# casio.net
KiCad netlist of a schematic drawn in Altium Designer
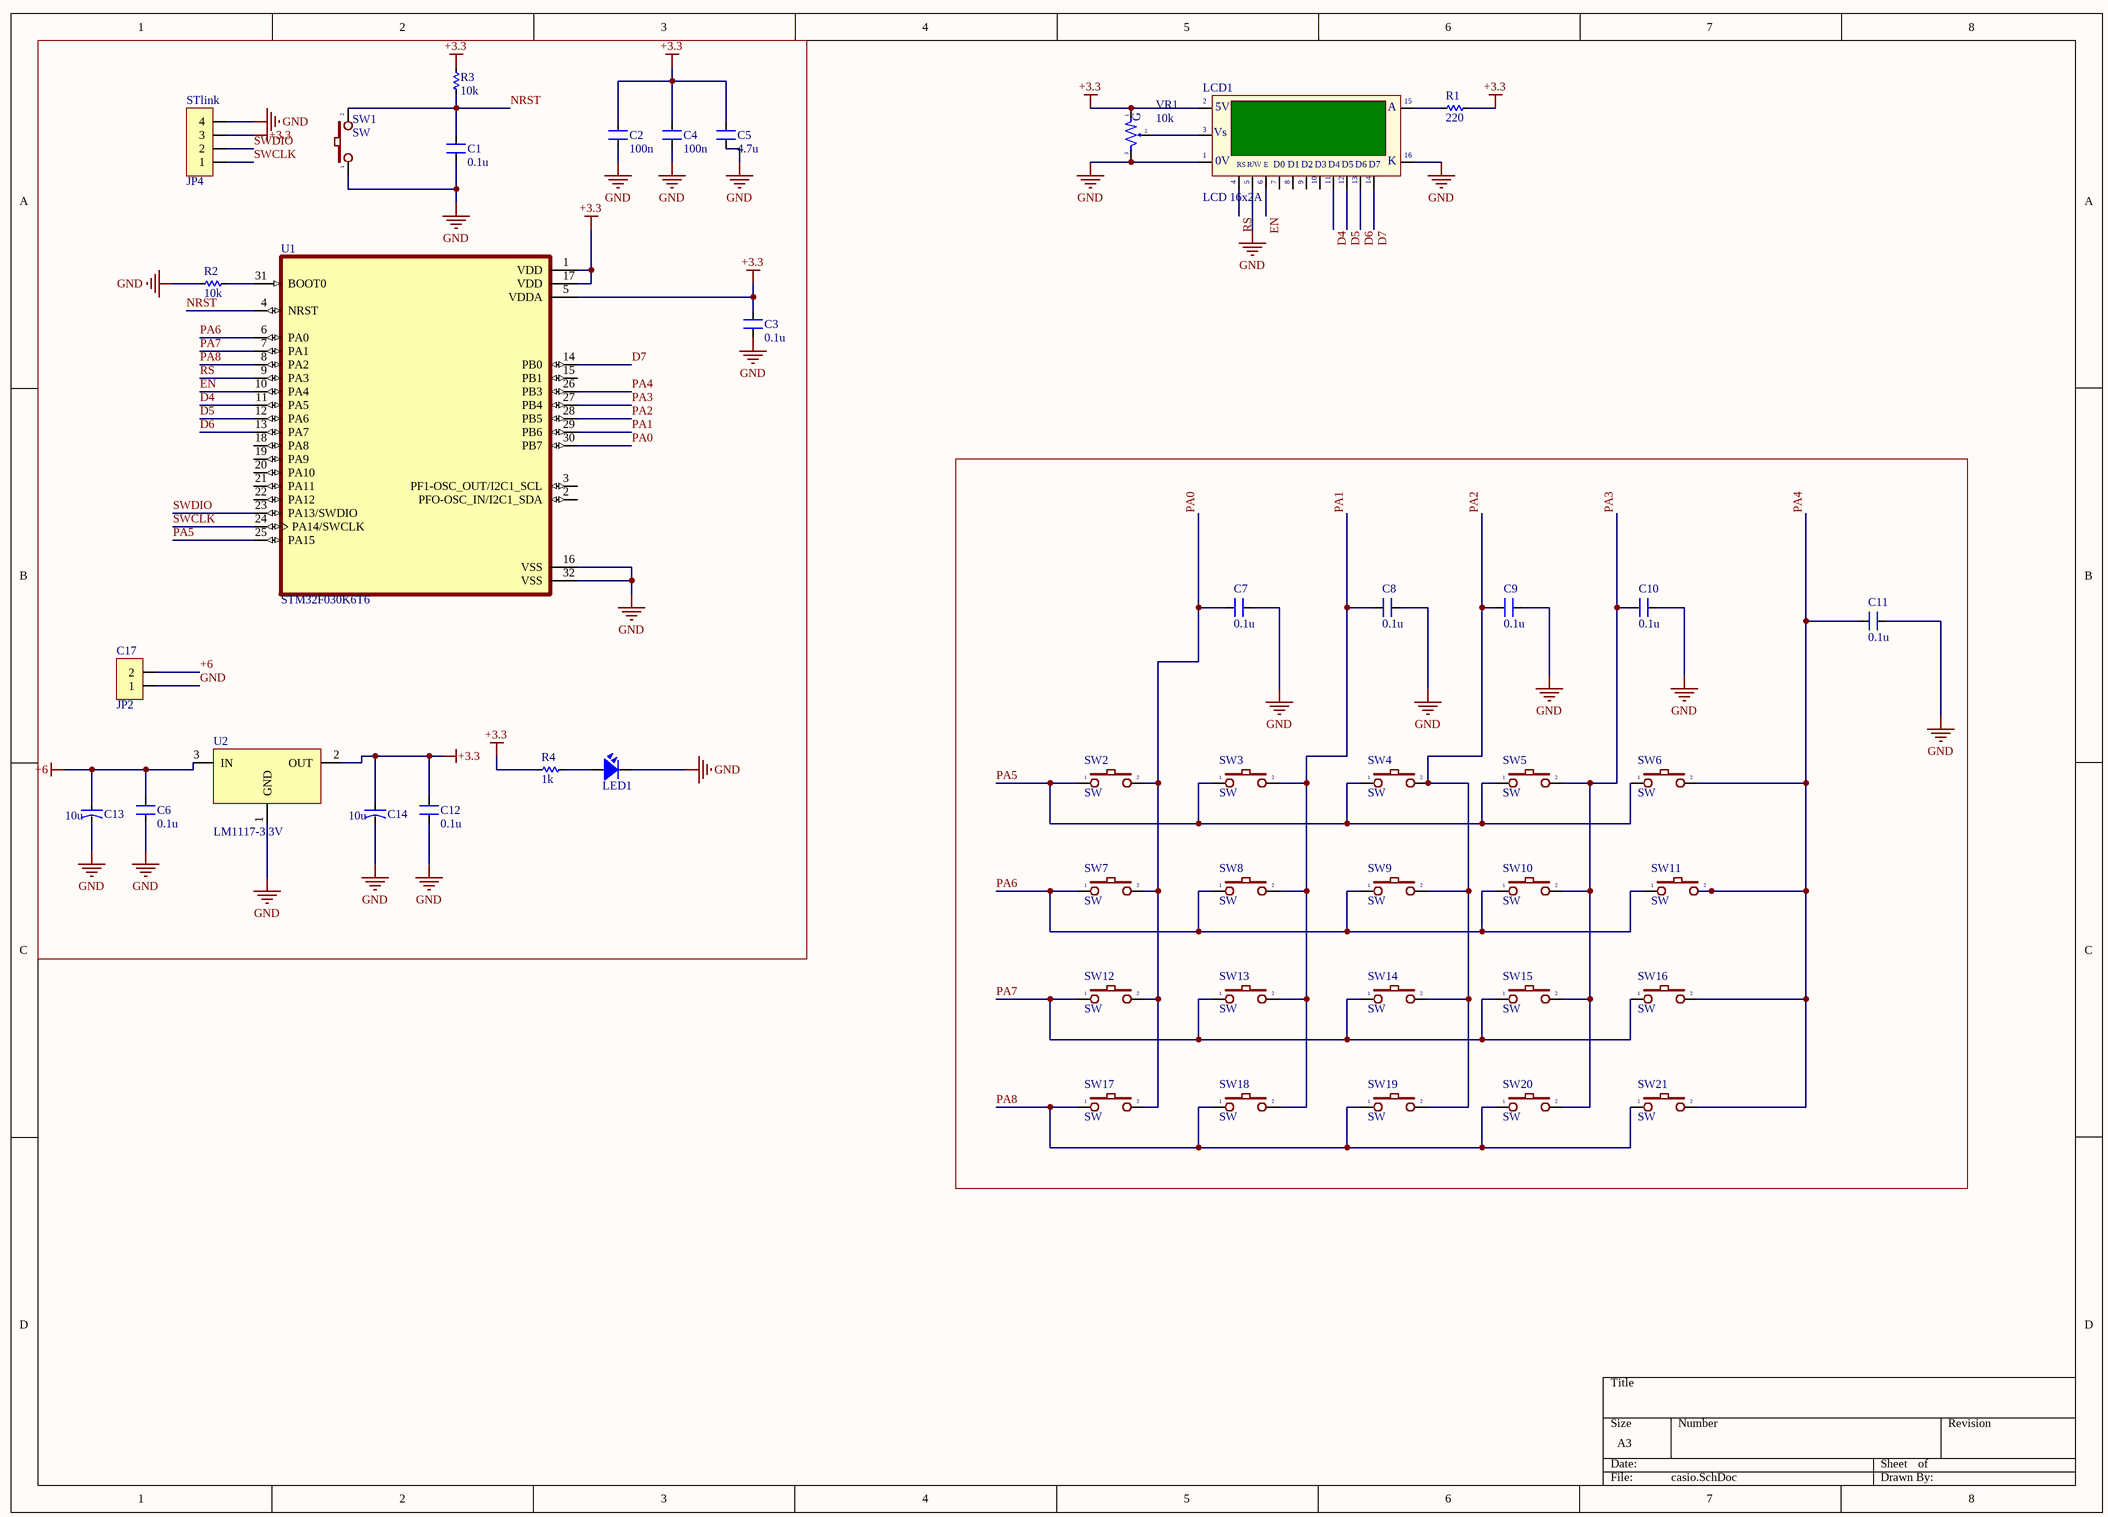
[diagram p0: casio.SchDoc]

(export (version "E")
  (design (tool "Eeschema 10.0.6"))
  (components
    (comp (ref "C1") (value "0.1u") (footprint "CN-SMD-0805") (libsource (lib "Library") (part "CN")))
    (comp (ref "C2") (value "100n") (footprint "CN-SMD-0805") (libsource (lib "Library") (part "CN")))
    (comp (ref "C3") (value "0.1u") (footprint "CN-SMD-0805") (libsource (lib "Library") (part "CN")))
    (comp (ref "C4") (value "100n") (footprint "CN-SMD-0805") (libsource (lib "Library") (part "CN")))
    (comp (ref "C5") (value "4.7u") (footprint "CN-SMD-0805") (libsource (lib "Library") (part "CN")))
    (comp (ref "C6") (value "0.1u") (footprint "CN-SMD-0805") (libsource (lib "Library") (part "CN")))
    (comp (ref "C7") (value "0.1u") (footprint "CN-SMD-0805") (libsource (lib "Library") (part "CN")))
    (comp (ref "C8") (value "0.1u") (footprint "CN-SMD-0805") (libsource (lib "Library") (part "CN")))
    (comp (ref "C9") (value "0.1u") (footprint "CN-SMD-0805") (libsource (lib "Library") (part "CN")))
    (comp (ref "C10") (value "0.1u") (footprint "CN-SMD-0805") (libsource (lib "Library") (part "CN")))
    (comp (ref "C11") (value "0.1u") (footprint "CN-SMD-0805") (libsource (lib "Library") (part "CN")))
    (comp (ref "C12") (value "0.1u") (footprint "CN-SMD-0805") (libsource (lib "Library") (part "CN")))
    (comp (ref "C13")
      (value "10u")
      (footprint "CAP-ALU-SMD-5.5x5.5")
      (description "Polarized Capacitor (Axial)")
      (fields (field (name "PUBLISHER") "Altium Limited"))
      (libsource (lib "Library") (part "CN-SMD"))
    )
    (comp (ref "C14")
      (value "10u")
      (footprint "CAP-ALU-SMD-5.5x5.5")
      (description "Polarized Capacitor (Axial)")
      (fields (field (name "PUBLISHER") "Altium Limited"))
      (libsource (lib "Library") (part "CN-SMD"))
    )
    (comp (ref "C17")
      (value "JP2")
      (footprint "JP2-D1T")
      (description "WR-PHD 2.54 mm Angled Socket Header")
      (fields
        (field (name "MANUFACTURER") "Würth Elektronik eiSos GmbH")
        (field (name "PARTNO") "613002143121")
        (field (name "CREATED BY") "Karrer Zheng")
      )
      (libsource (lib "Library") (part "JP2"))
    )
    (comp (ref "LCD1")
      (value "LCD 16x2A")
      (footprint "LCD16X2")
      (description "LCD dipslay 16 char, 2 line")
      (libsource (lib "Library") (part "LCD16x2A"))
    )
    (comp (ref "LED1") (value "LED") (footprint "LED-0805-Red") (libsource (lib "Library") (part "LED SMD")))
    (comp (ref "R1")
      (value "220")
      (footprint "RES-SMD-0805")
      (description "Resistor")
      (fields
        (field (name "MANUFACTURER") "Generic Components")
        (field (name "PUBLISHER") "Altium Hobart Technology Centre")
      )
      (libsource (lib "Library") (part "Res-SMD"))
    )
    (comp (ref "R2")
      (value "10k")
      (footprint "RES-SMD-0805")
      (description "Resistor")
      (fields
        (field (name "MANUFACTURER") "Generic Components")
        (field (name "PUBLISHER") "Altium Hobart Technology Centre")
      )
      (libsource (lib "Library") (part "Res-SMD"))
    )
    (comp (ref "R3")
      (value "10k")
      (footprint "RES-SMD-0805")
      (description "Resistor")
      (fields
        (field (name "MANUFACTURER") "Generic Components")
        (field (name "PUBLISHER") "Altium Hobart Technology Centre")
      )
      (libsource (lib "Library") (part "Res-SMD"))
    )
    (comp (ref "R4")
      (value "1k")
      (footprint "RES-SMD-0805")
      (description "Resistor")
      (fields
        (field (name "MANUFACTURER") "Generic Components")
        (field (name "PUBLISHER") "Altium Hobart Technology Centre")
      )
      (libsource (lib "Library") (part "Res-SMD"))
    )
    (comp (ref "STlink")
      (value "JP4")
      (footprint "JP4-C1T")
      (description "WR-PHD 2.54 mm Angled Socket Header")
      (fields
        (field (name "MANUFACTURER") "Würth Elektronik eiSos GmbH")
        (field (name "PARTNO") "613004143121")
        (field (name "CREATED BY") "Karrer Zheng")
      )
      (libsource (lib "Library") (part "JP4"))
    )
    (comp (ref "SW1")
      (value "SW")
      (footprint "SW1-SMD")
      (description "Switch button 2 pin")
      (libsource (lib "Library") (part "SW2"))
    )
    (comp (ref "SW2")
      (value "SW")
      (footprint "SW1-DIP-12x12x8-Black")
      (description "Switch button 2 pin")
      (libsource (lib "Library") (part "SW2"))
    )
    (comp (ref "SW3")
      (value "SW")
      (footprint "SW1-DIP-12x12x8-Black")
      (description "Switch button 2 pin")
      (libsource (lib "Library") (part "SW2"))
    )
    (comp (ref "SW4")
      (value "SW")
      (footprint "SW1-DIP-12x12x8-Black")
      (description "Switch button 2 pin")
      (libsource (lib "Library") (part "SW2"))
    )
    (comp (ref "SW5")
      (value "SW")
      (footprint "SW1-DIP-12x12x8-Black")
      (description "Switch button 2 pin")
      (libsource (lib "Library") (part "SW2"))
    )
    (comp (ref "SW6")
      (value "SW")
      (footprint "SW1-DIP-12x12x8-Black")
      (description "Switch button 2 pin")
      (libsource (lib "Library") (part "SW2"))
    )
    (comp (ref "SW7")
      (value "SW")
      (footprint "SW1-DIP-12x12x8-Black")
      (description "Switch button 2 pin")
      (libsource (lib "Library") (part "SW2"))
    )
    (comp (ref "SW8")
      (value "SW")
      (footprint "SW1-DIP-12x12x8-Black")
      (description "Switch button 2 pin")
      (libsource (lib "Library") (part "SW2"))
    )
    (comp (ref "SW9")
      (value "SW")
      (footprint "SW1-DIP-12x12x8-Black")
      (description "Switch button 2 pin")
      (libsource (lib "Library") (part "SW2"))
    )
    (comp (ref "SW10")
      (value "SW")
      (footprint "SW1-DIP-12x12x8-Black")
      (description "Switch button 2 pin")
      (libsource (lib "Library") (part "SW2"))
    )
    (comp (ref "SW11")
      (value "SW")
      (footprint "SW1-DIP-12x12x8-Black")
      (description "Switch button 2 pin")
      (libsource (lib "Library") (part "SW2"))
    )
    (comp (ref "SW12")
      (value "SW")
      (footprint "SW1-DIP-12x12x8-Black")
      (description "Switch button 2 pin")
      (libsource (lib "Library") (part "SW2"))
    )
    (comp (ref "SW13")
      (value "SW")
      (footprint "SW1-DIP-12x12x8-Black")
      (description "Switch button 2 pin")
      (libsource (lib "Library") (part "SW2"))
    )
    (comp (ref "SW14")
      (value "SW")
      (footprint "SW1-DIP-12x12x8-Black")
      (description "Switch button 2 pin")
      (libsource (lib "Library") (part "SW2"))
    )
    (comp (ref "SW15")
      (value "SW")
      (footprint "SW1-DIP-12x12x8-Black")
      (description "Switch button 2 pin")
      (libsource (lib "Library") (part "SW2"))
    )
    (comp (ref "SW16")
      (value "SW")
      (footprint "SW1-DIP-12x12x8-Black")
      (description "Switch button 2 pin")
      (libsource (lib "Library") (part "SW2"))
    )
    (comp (ref "SW17")
      (value "SW")
      (footprint "SW1-DIP-12x12x8-Black")
      (description "Switch button 2 pin")
      (libsource (lib "Library") (part "SW2"))
    )
    (comp (ref "SW18")
      (value "SW")
      (footprint "SW1-DIP-12x12x8-Black")
      (description "Switch button 2 pin")
      (libsource (lib "Library") (part "SW2"))
    )
    (comp (ref "SW19")
      (value "SW")
      (footprint "SW1-DIP-12x12x8-Black")
      (description "Switch button 2 pin")
      (libsource (lib "Library") (part "SW2"))
    )
    (comp (ref "SW20")
      (value "SW")
      (footprint "SW1-DIP-12x12x8-Black")
      (description "Switch button 2 pin")
      (libsource (lib "Library") (part "SW2"))
    )
    (comp (ref "SW21")
      (value "SW")
      (footprint "SW1-DIP-12x12x8-Black")
      (description "Switch button 2 pin")
      (libsource (lib "Library") (part "SW2"))
    )
    (comp (ref "U1")
      (value "STM32F030K6T6")
      (footprint "QFP80P900X900X160-32N")
      (fields (field (name "DIGI-KEY_PART_NUMBER") "497-14046-ND") (field (name "MF") "STMicroelectronics"))
      (libsource (lib "Library") (part "STM32F030K6T6"))
    )
    (comp (ref "U2")
      (value "LM1117-3.3V")
      (footprint "SOT223")
      (description "800mA Low-Dropout Linear Regulator")
      (fields (field (name "CREATOR") "Nguyen Ba Bien"))
      (libsource (lib "Library") (part "LM1117"))
    )
    (comp (ref "VR1")
      (value "10k")
      (footprint "VR-S2")
      (description "Var Resistor")
      (libsource (lib "Library") (part "VR-S"))
    )
  )
  (nets
    (net (code "1") (name "+3.3") (class "Default")
      (node (ref "C12") (pin "1") (pinfunction "1_1") (pintype "passive"))
      (node (ref "C14") (pin "1") (pinfunction "1_1") (pintype "passive"))
      (node (ref "C2") (pin "1") (pinfunction "1_1") (pintype "passive"))
      (node (ref "C3") (pin "1") (pinfunction "1_1") (pintype "passive"))
      (node (ref "C4") (pin "1") (pinfunction "1_1") (pintype "passive"))
      (node (ref "C5") (pin "1") (pinfunction "1_1") (pintype "passive"))
      (node (ref "LCD1") (pin "2") (pinfunction "VDD_2") (pintype "passive"))
      (node (ref "R1") (pin "1") (pinfunction "1_1") (pintype "passive"))
      (node (ref "R3") (pin "2") (pinfunction "2_2") (pintype "passive"))
      (node (ref "R4") (pin "2") (pinfunction "2_2") (pintype "passive"))
      (node (ref "STlink") (pin "3") (pinfunction "3_3") (pintype "passive"))
      (node (ref "U1") (pin "1") (pinfunction "VDD_1") (pintype "power_in"))
      (node (ref "U1") (pin "17") (pinfunction "VDD_17") (pintype "power_in"))
      (node (ref "U1") (pin "5") (pinfunction "VDDA_5") (pintype "power_in"))
      (node (ref "U2") (pin "2") (pinfunction "OUT_2") (pintype "passive"))
      (node (ref "VR1") (pin "1") (pinfunction "1_1") (pintype "passive"))
    )
    (net (code "2") (name "+6") (class "Default")
      (node (ref "C13") (pin "1") (pinfunction "1_1") (pintype "passive"))
      (node (ref "C17") (pin "2") (pinfunction "2_2") (pintype "passive"))
      (node (ref "C6") (pin "1") (pinfunction "1_1") (pintype "passive"))
      (node (ref "U2") (pin "3") (pinfunction "IN_3") (pintype "passive"))
    )
    (net (code "3") (name "/D4") (class "Default")
      (node (ref "LCD1") (pin "11") (pinfunction "D4_11") (pintype "passive"))
      (node (ref "U1") (pin "11") (pinfunction "PA5_11") (pintype "bidirectional"))
    )
    (net (code "4") (name "/D5") (class "Default")
      (node (ref "LCD1") (pin "12") (pinfunction "D5_12") (pintype "passive"))
      (node (ref "U1") (pin "12") (pinfunction "PA6_12") (pintype "bidirectional"))
    )
    (net (code "5") (name "/D6") (class "Default")
      (node (ref "LCD1") (pin "13") (pinfunction "D6_13") (pintype "passive"))
      (node (ref "U1") (pin "13") (pinfunction "PA7_13") (pintype "bidirectional"))
    )
    (net (code "6") (name "/D7") (class "Default")
      (node (ref "LCD1") (pin "14") (pinfunction "D7_14") (pintype "passive"))
      (node (ref "U1") (pin "14") (pinfunction "PB0_14") (pintype "bidirectional"))
    )
    (net (code "7") (name "/EN") (class "Default")
      (node (ref "LCD1") (pin "6") (pinfunction "~{EN}_6") (pintype "passive"))
      (node (ref "U1") (pin "10") (pinfunction "PA4_10") (pintype "bidirectional"))
    )
    (net (code "8") (name "/NRST") (class "Default")
      (node (ref "C1") (pin "1") (pinfunction "1_1") (pintype "passive"))
      (node (ref "R3") (pin "1") (pinfunction "1_1") (pintype "passive"))
      (node (ref "SW1") (pin "2") (pinfunction "2_2") (pintype "passive"))
      (node (ref "U1") (pin "4") (pinfunction "NRST_4") (pintype "bidirectional"))
    )
    (net (code "9") (name "/PA0") (class "Default")
      (node (ref "C7") (pin "1") (pinfunction "1_1") (pintype "passive"))
      (node (ref "SW12") (pin "2") (pinfunction "2_2") (pintype "passive"))
      (node (ref "SW17") (pin "2") (pinfunction "2_2") (pintype "passive"))
      (node (ref "SW2") (pin "2") (pinfunction "2_2") (pintype "passive"))
      (node (ref "SW7") (pin "2") (pinfunction "2_2") (pintype "passive"))
      (node (ref "U1") (pin "30") (pinfunction "PB7_30") (pintype "bidirectional"))
    )
    (net (code "10") (name "/PA1") (class "Default")
      (node (ref "C8") (pin "1") (pinfunction "1_1") (pintype "passive"))
      (node (ref "SW13") (pin "2") (pinfunction "2_2") (pintype "passive"))
      (node (ref "SW18") (pin "2") (pinfunction "2_2") (pintype "passive"))
      (node (ref "SW3") (pin "2") (pinfunction "2_2") (pintype "passive"))
      (node (ref "SW8") (pin "2") (pinfunction "2_2") (pintype "passive"))
      (node (ref "U1") (pin "29") (pinfunction "PB6_29") (pintype "bidirectional"))
    )
    (net (code "11") (name "/PA2") (class "Default")
      (node (ref "C9") (pin "1") (pinfunction "1_1") (pintype "passive"))
      (node (ref "SW14") (pin "2") (pinfunction "2_2") (pintype "passive"))
      (node (ref "SW19") (pin "2") (pinfunction "2_2") (pintype "passive"))
      (node (ref "SW4") (pin "2") (pinfunction "2_2") (pintype "passive"))
      (node (ref "SW9") (pin "2") (pinfunction "2_2") (pintype "passive"))
      (node (ref "U1") (pin "28") (pinfunction "PB5_28") (pintype "bidirectional"))
    )
    (net (code "12") (name "/PA3") (class "Default")
      (node (ref "C10") (pin "1") (pinfunction "1_1") (pintype "passive"))
      (node (ref "SW10") (pin "2") (pinfunction "2_2") (pintype "passive"))
      (node (ref "SW15") (pin "2") (pinfunction "2_2") (pintype "passive"))
      (node (ref "SW20") (pin "2") (pinfunction "2_2") (pintype "passive"))
      (node (ref "SW5") (pin "2") (pinfunction "2_2") (pintype "passive"))
      (node (ref "U1") (pin "27") (pinfunction "PB4_27") (pintype "bidirectional"))
    )
    (net (code "13") (name "/PA4") (class "Default")
      (node (ref "C11") (pin "1") (pinfunction "1_1") (pintype "passive"))
      (node (ref "SW11") (pin "2") (pinfunction "2_2") (pintype "passive"))
      (node (ref "SW16") (pin "2") (pinfunction "2_2") (pintype "passive"))
      (node (ref "SW21") (pin "2") (pinfunction "2_2") (pintype "passive"))
      (node (ref "SW6") (pin "2") (pinfunction "2_2") (pintype "passive"))
      (node (ref "U1") (pin "26") (pinfunction "PB3_26") (pintype "bidirectional"))
    )
    (net (code "14") (name "/PA5") (class "Default")
      (node (ref "SW2") (pin "1") (pinfunction "1_1") (pintype "passive"))
      (node (ref "SW3") (pin "1") (pinfunction "1_1") (pintype "passive"))
      (node (ref "SW4") (pin "1") (pinfunction "1_1") (pintype "passive"))
      (node (ref "SW5") (pin "1") (pinfunction "1_1") (pintype "passive"))
      (node (ref "SW6") (pin "1") (pinfunction "1_1") (pintype "passive"))
      (node (ref "U1") (pin "25") (pinfunction "PA15_25") (pintype "bidirectional"))
    )
    (net (code "15") (name "/PA6") (class "Default")
      (node (ref "SW10") (pin "1") (pinfunction "1_1") (pintype "passive"))
      (node (ref "SW11") (pin "1") (pinfunction "1_1") (pintype "passive"))
      (node (ref "SW7") (pin "1") (pinfunction "1_1") (pintype "passive"))
      (node (ref "SW8") (pin "1") (pinfunction "1_1") (pintype "passive"))
      (node (ref "SW9") (pin "1") (pinfunction "1_1") (pintype "passive"))
      (node (ref "U1") (pin "6") (pinfunction "PA0_6") (pintype "bidirectional"))
    )
    (net (code "16") (name "/PA7") (class "Default")
      (node (ref "SW12") (pin "1") (pinfunction "1_1") (pintype "passive"))
      (node (ref "SW13") (pin "1") (pinfunction "1_1") (pintype "passive"))
      (node (ref "SW14") (pin "1") (pinfunction "1_1") (pintype "passive"))
      (node (ref "SW15") (pin "1") (pinfunction "1_1") (pintype "passive"))
      (node (ref "SW16") (pin "1") (pinfunction "1_1") (pintype "passive"))
      (node (ref "U1") (pin "7") (pinfunction "PA1_7") (pintype "bidirectional"))
    )
    (net (code "17") (name "/PA8") (class "Default")
      (node (ref "SW17") (pin "1") (pinfunction "1_1") (pintype "passive"))
      (node (ref "SW18") (pin "1") (pinfunction "1_1") (pintype "passive"))
      (node (ref "SW19") (pin "1") (pinfunction "1_1") (pintype "passive"))
      (node (ref "SW20") (pin "1") (pinfunction "1_1") (pintype "passive"))
      (node (ref "SW21") (pin "1") (pinfunction "1_1") (pintype "passive"))
      (node (ref "U1") (pin "8") (pinfunction "PA2_8") (pintype "bidirectional"))
    )
    (net (code "18") (name "/RS") (class "Default")
      (node (ref "LCD1") (pin "4") (pinfunction "RS_4") (pintype "passive"))
      (node (ref "U1") (pin "9") (pinfunction "PA3_9") (pintype "bidirectional"))
    )
    (net (code "19") (name "/SWCLK") (class "Default")
      (node (ref "STlink") (pin "1") (pinfunction "1_1") (pintype "passive"))
      (node (ref "U1") (pin "24") (pinfunction "PA14/SWCLK_24") (pintype "bidirectional"))
    )
    (net (code "20") (name "/SWDIO") (class "Default")
      (node (ref "STlink") (pin "2") (pinfunction "2_2") (pintype "passive"))
      (node (ref "U1") (pin "23") (pinfunction "PA13/SWDIO_23") (pintype "bidirectional"))
    )
    (net (code "21") (name "GND") (class "Default")
      (node (ref "C1") (pin "2") (pinfunction "2_2") (pintype "passive"))
      (node (ref "C10") (pin "2") (pinfunction "2_2") (pintype "passive"))
      (node (ref "C11") (pin "2") (pinfunction "2_2") (pintype "passive"))
      (node (ref "C12") (pin "2") (pinfunction "2_2") (pintype "passive"))
      (node (ref "C13") (pin "2") (pinfunction "2_2") (pintype "passive"))
      (node (ref "C14") (pin "2") (pinfunction "2_2") (pintype "passive"))
      (node (ref "C17") (pin "1") (pinfunction "1_1") (pintype "passive"))
      (node (ref "C2") (pin "2") (pinfunction "2_2") (pintype "passive"))
      (node (ref "C3") (pin "2") (pinfunction "2_2") (pintype "passive"))
      (node (ref "C4") (pin "2") (pinfunction "2_2") (pintype "passive"))
      (node (ref "C5") (pin "2") (pinfunction "2_2") (pintype "passive"))
      (node (ref "C6") (pin "2") (pinfunction "2_2") (pintype "passive"))
      (node (ref "C7") (pin "2") (pinfunction "2_2") (pintype "passive"))
      (node (ref "C8") (pin "2") (pinfunction "2_2") (pintype "passive"))
      (node (ref "C9") (pin "2") (pinfunction "2_2") (pintype "passive"))
      (node (ref "LCD1") (pin "1") (pinfunction "GND_1") (pintype "passive"))
      (node (ref "LCD1") (pin "16") (pinfunction "K_16") (pintype "passive"))
      (node (ref "LCD1") (pin "5") (pinfunction "R/~{W}_5") (pintype "passive"))
      (node (ref "LED1") (pin "2") (pinfunction "2_2") (pintype "passive"))
      (node (ref "R2") (pin "2") (pinfunction "2_2") (pintype "passive"))
      (node (ref "STlink") (pin "4") (pinfunction "4_4") (pintype "passive"))
      (node (ref "SW1") (pin "1") (pinfunction "1_1") (pintype "passive"))
      (node (ref "U1") (pin "16") (pinfunction "VSS_16") (pintype "power_in"))
      (node (ref "U1") (pin "32") (pinfunction "VSS_32") (pintype "power_in"))
      (node (ref "U2") (pin "1") (pinfunction "GND_1") (pintype "passive"))
      (node (ref "VR1") (pin "3") (pinfunction "3_3") (pintype "passive"))
    )
    (net (code "22") (name "Net-(LCD1-A)") (class "Default")
      (node (ref "LCD1") (pin "15") (pinfunction "A_15") (pintype "passive"))
      (node (ref "R1") (pin "2") (pinfunction "2_2") (pintype "passive"))
    )
    (net (code "23") (name "Net-(LCD1-VEE)") (class "Default")
      (node (ref "LCD1") (pin "3") (pinfunction "VEE_3") (pintype "passive"))
      (node (ref "VR1") (pin "2") (pinfunction "2_2") (pintype "passive"))
    )
    (net (code "24") (name "Net-(LED1-Pad1)") (class "Default")
      (node (ref "LED1") (pin "1") (pinfunction "1_1") (pintype "passive"))
      (node (ref "R4") (pin "1") (pinfunction "1_1") (pintype "passive"))
    )
    (net (code "25") (name "Net-(U1-BOOT0)") (class "Default")
      (node (ref "R2") (pin "1") (pinfunction "1_1") (pintype "passive"))
      (node (ref "U1") (pin "31") (pinfunction "BOOT0_31") (pintype "input"))
    )
    (net (code "26") (name "unconnected-(LCD1-D0-Pad7)") (class "Default")
      (node (ref "LCD1") (pin "7") (pinfunction "D0_7") (pintype "passive"))
    )
    (net (code "27") (name "unconnected-(LCD1-D1-Pad8)") (class "Default")
      (node (ref "LCD1") (pin "8") (pinfunction "D1_8") (pintype "passive"))
    )
    (net (code "28") (name "unconnected-(LCD1-D2-Pad9)") (class "Default")
      (node (ref "LCD1") (pin "9") (pinfunction "D2_9") (pintype "passive"))
    )
    (net (code "29") (name "unconnected-(LCD1-D3-Pad10)") (class "Default")
      (node (ref "LCD1") (pin "10") (pinfunction "D3_10") (pintype "passive"))
    )
    (net (code "30") (name "unconnected-(U1-PA8-Pad18)") (class "Default")
      (node (ref "U1") (pin "18") (pinfunction "PA8_18") (pintype "bidirectional"))
    )
    (net (code "31") (name "unconnected-(U1-PA9-Pad19)") (class "Default")
      (node (ref "U1") (pin "19") (pinfunction "PA9_19") (pintype "bidirectional"))
    )
    (net (code "32") (name "unconnected-(U1-PA10-Pad20)") (class "Default")
      (node (ref "U1") (pin "20") (pinfunction "PA10_20") (pintype "bidirectional"))
    )
    (net (code "33") (name "unconnected-(U1-PA11-Pad21)") (class "Default")
      (node (ref "U1") (pin "21") (pinfunction "PA11_21") (pintype "bidirectional"))
    )
    (net (code "34") (name "unconnected-(U1-PA12-Pad22)") (class "Default")
      (node (ref "U1") (pin "22") (pinfunction "PA12_22") (pintype "bidirectional"))
    )
    (net (code "35") (name "unconnected-(U1-PB1-Pad15)") (class "Default")
      (node (ref "U1") (pin "15") (pinfunction "PB1_15") (pintype "bidirectional"))
    )
    (net (code "36") (name "unconnected-(U1-PF1-OSC_OUT{slash}I2C1_SCL-Pad3)") (class "Default")
      (node (ref "U1") (pin "3") (pinfunction "PF1-OSC_OUT/I2C1_SCL_3") (pintype "bidirectional"))
    )
    (net (code "37") (name "unconnected-(U1-PFO-OSC_IN{slash}I2C1_SDA-Pad2)") (class "Default")
      (node (ref "U1") (pin "2") (pinfunction "PFO-OSC_IN/I2C1_SDA_2") (pintype "bidirectional"))
    )
  )
)
